# board2sided.net
KiCad netlist of a schematic drawn in EAGLE
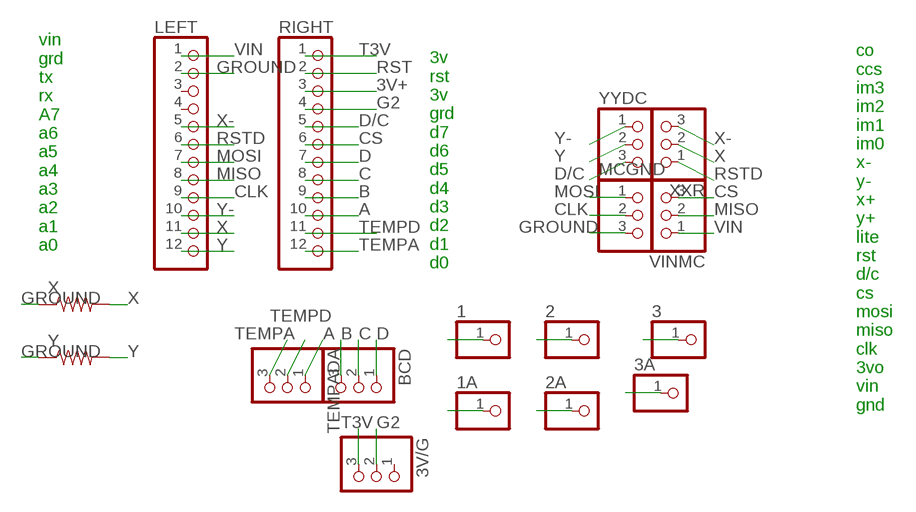
[diagram p0: schematic, sheet 1]

(export (version "E")
  (design (tool "Eeschema 10.0.6"))
  (components
    (comp (ref "1")
      (value "PINHD-1X1CB")
      (footprint "eagle-import:1X01-CLEANBIG")
      (libsource (lib "eagle-import") (part "PINHD-1X1CB"))
    )
    (comp (ref "1A")
      (value "PINHD-1X1CB")
      (footprint "eagle-import:1X01-CLEANBIG")
      (libsource (lib "eagle-import") (part "PINHD-1X1CB"))
    )
    (comp (ref "2")
      (value "PINHD-1X1CB")
      (footprint "eagle-import:1X01-CLEANBIG")
      (libsource (lib "eagle-import") (part "PINHD-1X1CB"))
    )
    (comp (ref "2A")
      (value "PINHD-1X1CB")
      (footprint "eagle-import:1X01-CLEANBIG")
      (libsource (lib "eagle-import") (part "PINHD-1X1CB"))
    )
    (comp (ref "3")
      (value "PINHD-1X1CB")
      (footprint "eagle-import:1X01-CLEANBIG")
      (libsource (lib "eagle-import") (part "PINHD-1X1CB"))
    )
    (comp (ref "3A")
      (value "PINHD-1X1CB")
      (footprint "eagle-import:1X01-CLEANBIG")
      (libsource (lib "eagle-import") (part "PINHD-1X1CB"))
    )
    (comp (ref "3V/G")
      (value "PINHD-1X3CB")
      (footprint "eagle-import:1X03-CLEANBIG")
      (libsource (lib "eagle-import") (part "PINHD-1X3CB"))
    )
    (comp (ref "BCD")
      (value "PINHD-1X3CB")
      (footprint "eagle-import:1X03-CLEANBIG")
      (libsource (lib "eagle-import") (part "PINHD-1X3CB"))
    )
    (comp (ref "LEFT")
      (value "PINHD-1X12-CB")
      (footprint "eagle-import:1X12-CB")
      (libsource (lib "eagle-import") (part "PINHD-1X12-CB"))
    )
    (comp (ref "MCGND")
      (value "PINHD-1X3CB")
      (footprint "eagle-import:1X03-CLEANBIG")
      (libsource (lib "eagle-import") (part "PINHD-1X3CB"))
    )
    (comp (ref "RIGHT")
      (value "PINHD-1X12-CB")
      (footprint "eagle-import:1X12-CB")
      (libsource (lib "eagle-import") (part "PINHD-1X12-CB"))
    )
    (comp (ref "TEMPADA")
      (value "PINHD-1X3CB")
      (footprint "eagle-import:1X03-CLEANBIG")
      (libsource (lib "eagle-import") (part "PINHD-1X3CB"))
    )
    (comp (ref "VINMC")
      (value "PINHD-1X3CB")
      (footprint "eagle-import:1X03-CLEANBIG")
      (libsource (lib "eagle-import") (part "PINHD-1X3CB"))
    )
    (comp (ref "X")
      (value "10KOHM-1/6W-5%(PTH)KIT")
      (footprint "eagle-import:AXIAL-0.3-KIT")
      (libsource (lib "eagle-import") (part "10KOHM-1/6W-5%(PTH)KIT"))
    )
    (comp (ref "XXR")
      (value "PINHD-1X3CB")
      (footprint "eagle-import:1X03-CLEANBIG")
      (libsource (lib "eagle-import") (part "PINHD-1X3CB"))
    )
    (comp (ref "Y")
      (value "10KOHM-1/6W-5%(PTH)KIT")
      (footprint "eagle-import:AXIAL-0.3-KIT")
      (libsource (lib "eagle-import") (part "10KOHM-1/6W-5%(PTH)KIT"))
    )
    (comp (ref "YYDC")
      (value "PINHD-1X3CB")
      (footprint "eagle-import:1X03-CLEANBIG")
      (libsource (lib "eagle-import") (part "PINHD-1X3CB"))
    )
  )
  (nets
    (net (code "1") (name "/1") (class "Default")
      (node (ref "1") (pin "1") (pinfunction "1_1") (pintype "passive"))
      (node (ref "1A") (pin "1") (pinfunction "1_1") (pintype "passive"))
    )
    (net (code "2") (name "/2") (class "Default")
      (node (ref "2") (pin "1") (pinfunction "1_1") (pintype "passive"))
      (node (ref "2A") (pin "1") (pinfunction "1_1") (pintype "passive"))
    )
    (net (code "3") (name "/3") (class "Default")
      (node (ref "3") (pin "1") (pinfunction "1_1") (pintype "passive"))
      (node (ref "3A") (pin "1") (pinfunction "1_1") (pintype "passive"))
    )
    (net (code "4") (name "/3V+") (class "Default")
      (node (ref "RIGHT") (pin "3") (pinfunction "3_3") (pintype "passive"))
    )
    (net (code "5") (name "/A") (class "Default")
      (node (ref "RIGHT") (pin "10") (pinfunction "10_10") (pintype "passive"))
      (node (ref "TEMPADA") (pin "1") (pinfunction "1_1") (pintype "passive"))
    )
    (net (code "6") (name "/B") (class "Default")
      (node (ref "BCD") (pin "3") (pinfunction "3_3") (pintype "passive"))
      (node (ref "RIGHT") (pin "9") (pinfunction "9_9") (pintype "passive"))
    )
    (net (code "7") (name "/C") (class "Default")
      (node (ref "BCD") (pin "2") (pinfunction "2_2") (pintype "passive"))
      (node (ref "RIGHT") (pin "8") (pinfunction "8_8") (pintype "passive"))
    )
    (net (code "8") (name "/CLK") (class "Default")
      (node (ref "LEFT") (pin "9") (pinfunction "9_9") (pintype "passive"))
      (node (ref "MCGND") (pin "2") (pinfunction "2_2") (pintype "passive"))
    )
    (net (code "9") (name "/CS") (class "Default")
      (node (ref "RIGHT") (pin "6") (pinfunction "6_6") (pintype "passive"))
      (node (ref "VINMC") (pin "3") (pinfunction "3_3") (pintype "passive"))
    )
    (net (code "10") (name "/D") (class "Default")
      (node (ref "BCD") (pin "1") (pinfunction "1_1") (pintype "passive"))
      (node (ref "RIGHT") (pin "7") (pinfunction "7_7") (pintype "passive"))
    )
    (net (code "11") (name "/D{slash}C") (class "Default")
      (node (ref "RIGHT") (pin "5") (pinfunction "5_5") (pintype "passive"))
      (node (ref "YYDC") (pin "3") (pinfunction "3_3") (pintype "passive"))
    )
    (net (code "12") (name "/G2") (class "Default")
      (node (ref "3V/G") (pin "2") (pinfunction "2_2") (pintype "passive"))
      (node (ref "RIGHT") (pin "4") (pinfunction "4_4") (pintype "passive"))
    )
    (net (code "13") (name "/GROUND") (class "Default")
      (node (ref "LEFT") (pin "2") (pinfunction "2_2") (pintype "passive"))
      (node (ref "MCGND") (pin "3") (pinfunction "3_3") (pintype "passive"))
      (node (ref "X") (pin "P$1") (pinfunction "1_P$1") (pintype "passive"))
      (node (ref "Y") (pin "P$1") (pinfunction "1_P$1") (pintype "passive"))
    )
    (net (code "14") (name "/MISO") (class "Default")
      (node (ref "LEFT") (pin "8") (pinfunction "8_8") (pintype "passive"))
      (node (ref "VINMC") (pin "2") (pinfunction "2_2") (pintype "passive"))
    )
    (net (code "15") (name "/MOSI") (class "Default")
      (node (ref "LEFT") (pin "7") (pinfunction "7_7") (pintype "passive"))
      (node (ref "MCGND") (pin "1") (pinfunction "1_1") (pintype "passive"))
    )
    (net (code "16") (name "/RST") (class "Default")
      (node (ref "RIGHT") (pin "2") (pinfunction "2_2") (pintype "passive"))
    )
    (net (code "17") (name "/RSTD") (class "Default")
      (node (ref "LEFT") (pin "6") (pinfunction "6_6") (pintype "passive"))
      (node (ref "XXR") (pin "1") (pinfunction "1_1") (pintype "passive"))
    )
    (net (code "18") (name "/T3V") (class "Default")
      (node (ref "3V/G") (pin "3") (pinfunction "3_3") (pintype "passive"))
      (node (ref "RIGHT") (pin "1") (pinfunction "1_1") (pintype "passive"))
    )
    (net (code "19") (name "/TEMPA") (class "Default")
      (node (ref "RIGHT") (pin "12") (pinfunction "12_12") (pintype "passive"))
      (node (ref "TEMPADA") (pin "3") (pinfunction "3_3") (pintype "passive"))
    )
    (net (code "20") (name "/TEMPD") (class "Default")
      (node (ref "RIGHT") (pin "11") (pinfunction "11_11") (pintype "passive"))
      (node (ref "TEMPADA") (pin "2") (pinfunction "2_2") (pintype "passive"))
    )
    (net (code "21") (name "/VIN") (class "Default")
      (node (ref "LEFT") (pin "1") (pinfunction "1_1") (pintype "passive"))
      (node (ref "VINMC") (pin "1") (pinfunction "1_1") (pintype "passive"))
    )
    (net (code "22") (name "/X") (class "Default")
      (node (ref "LEFT") (pin "11") (pinfunction "11_11") (pintype "passive"))
      (node (ref "X") (pin "P$2") (pinfunction "2_P$2") (pintype "passive"))
      (node (ref "XXR") (pin "2") (pinfunction "2_2") (pintype "passive"))
    )
    (net (code "23") (name "/X-") (class "Default")
      (node (ref "LEFT") (pin "5") (pinfunction "5_5") (pintype "passive"))
      (node (ref "XXR") (pin "3") (pinfunction "3_3") (pintype "passive"))
    )
    (net (code "24") (name "/Y") (class "Default")
      (node (ref "LEFT") (pin "12") (pinfunction "12_12") (pintype "passive"))
      (node (ref "Y") (pin "P$2") (pinfunction "2_P$2") (pintype "passive"))
      (node (ref "YYDC") (pin "2") (pinfunction "2_2") (pintype "passive"))
    )
    (net (code "25") (name "/Y-") (class "Default")
      (node (ref "LEFT") (pin "10") (pinfunction "10_10") (pintype "passive"))
      (node (ref "YYDC") (pin "1") (pinfunction "1_1") (pintype "passive"))
    )
    (net (code "26") (name "unconnected-(3V/G-Pad1)") (class "Default")
      (node (ref "3V/G") (pin "1") (pinfunction "1_1") (pintype "passive"))
    )
    (net (code "27") (name "unconnected-(LEFT-Pad3)") (class "Default")
      (node (ref "LEFT") (pin "3") (pinfunction "3_3") (pintype "passive"))
    )
    (net (code "28") (name "unconnected-(LEFT-Pad4)") (class "Default")
      (node (ref "LEFT") (pin "4") (pinfunction "4_4") (pintype "passive"))
    )
  )
)
